# WarpDrive_201903.net
KiCad netlist of a schematic drawn in EAGLE
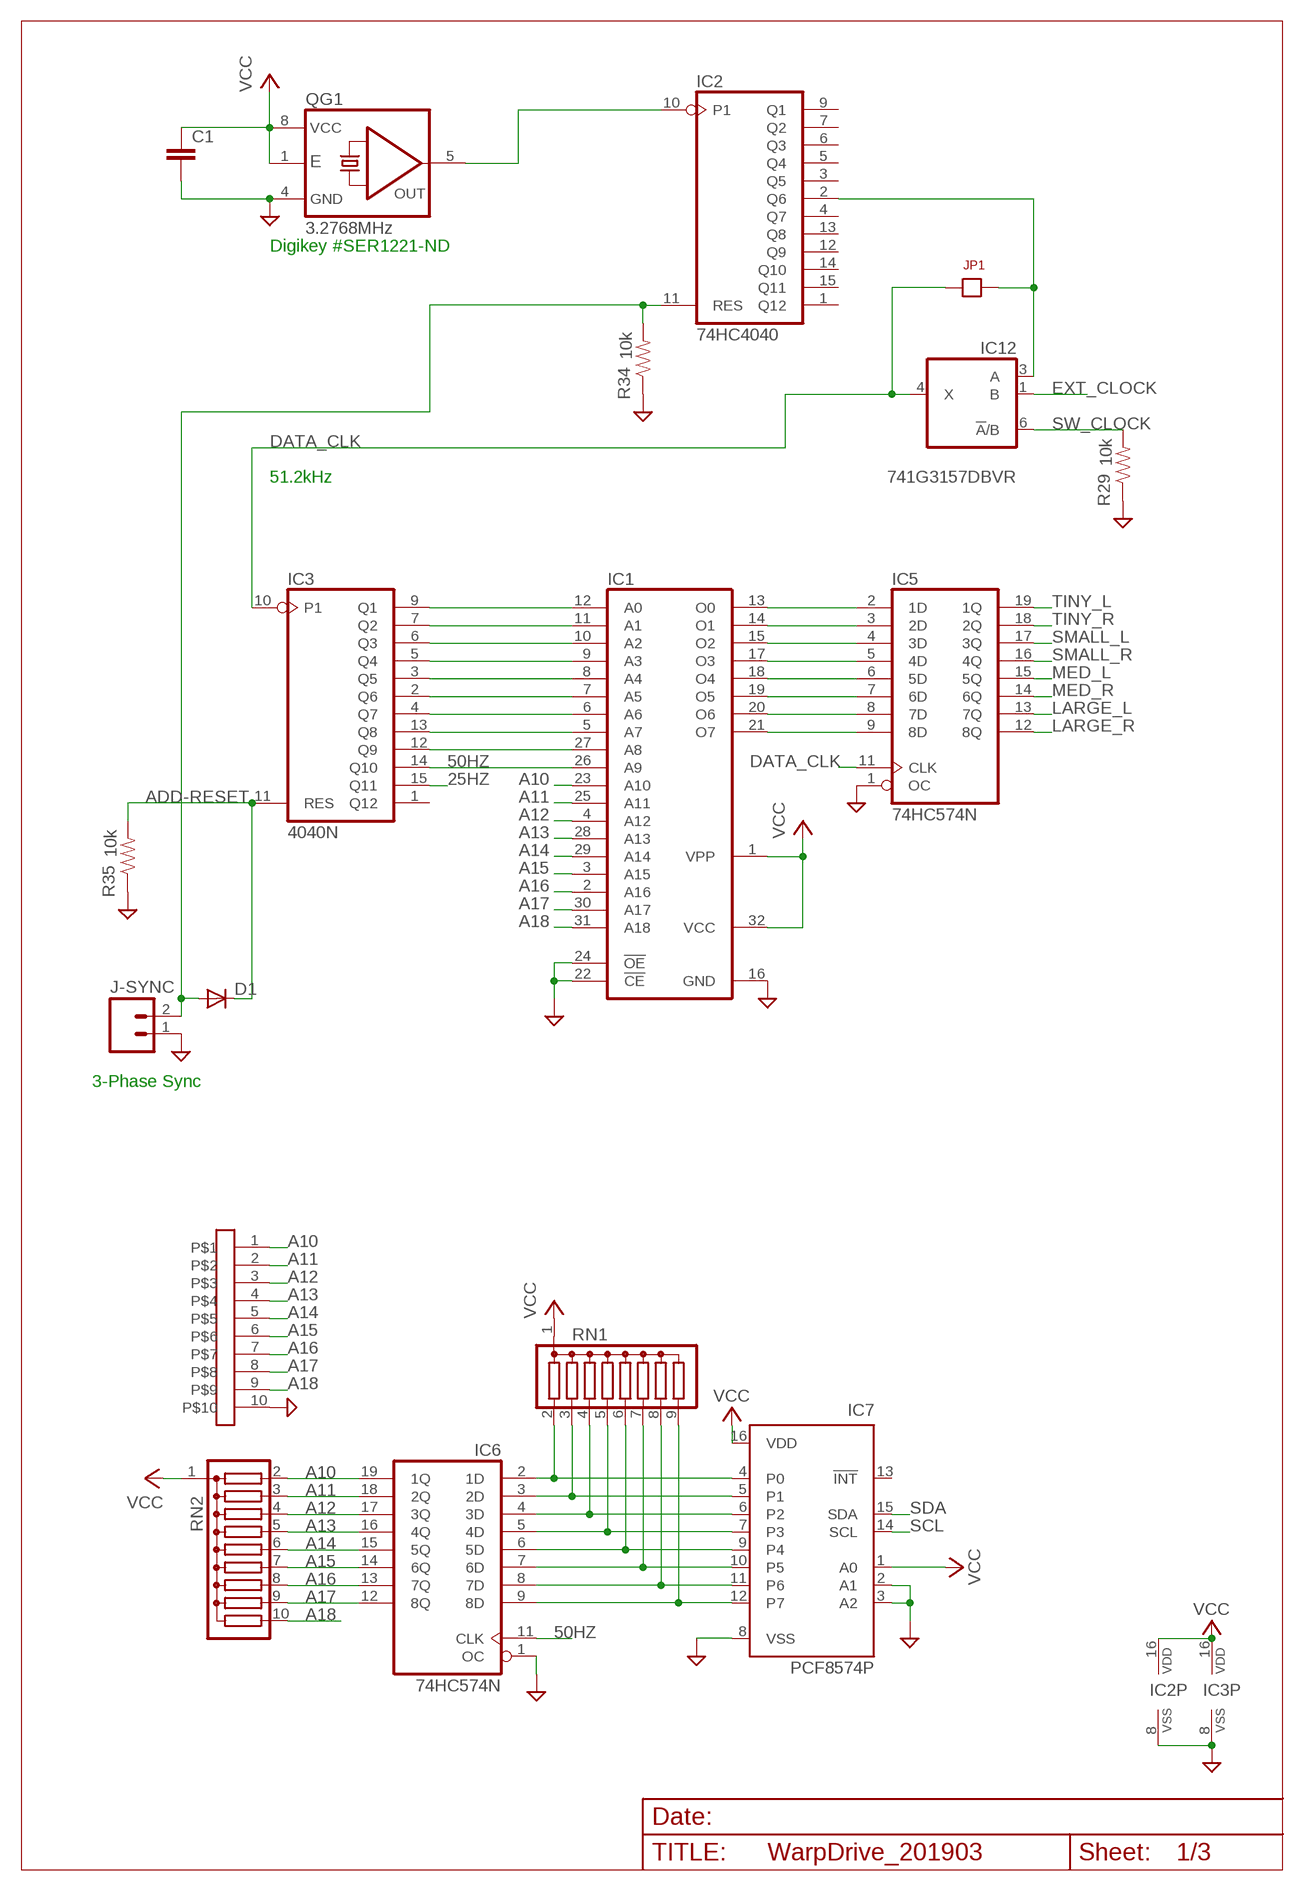
[diagram p0: schematic, sheet 1]
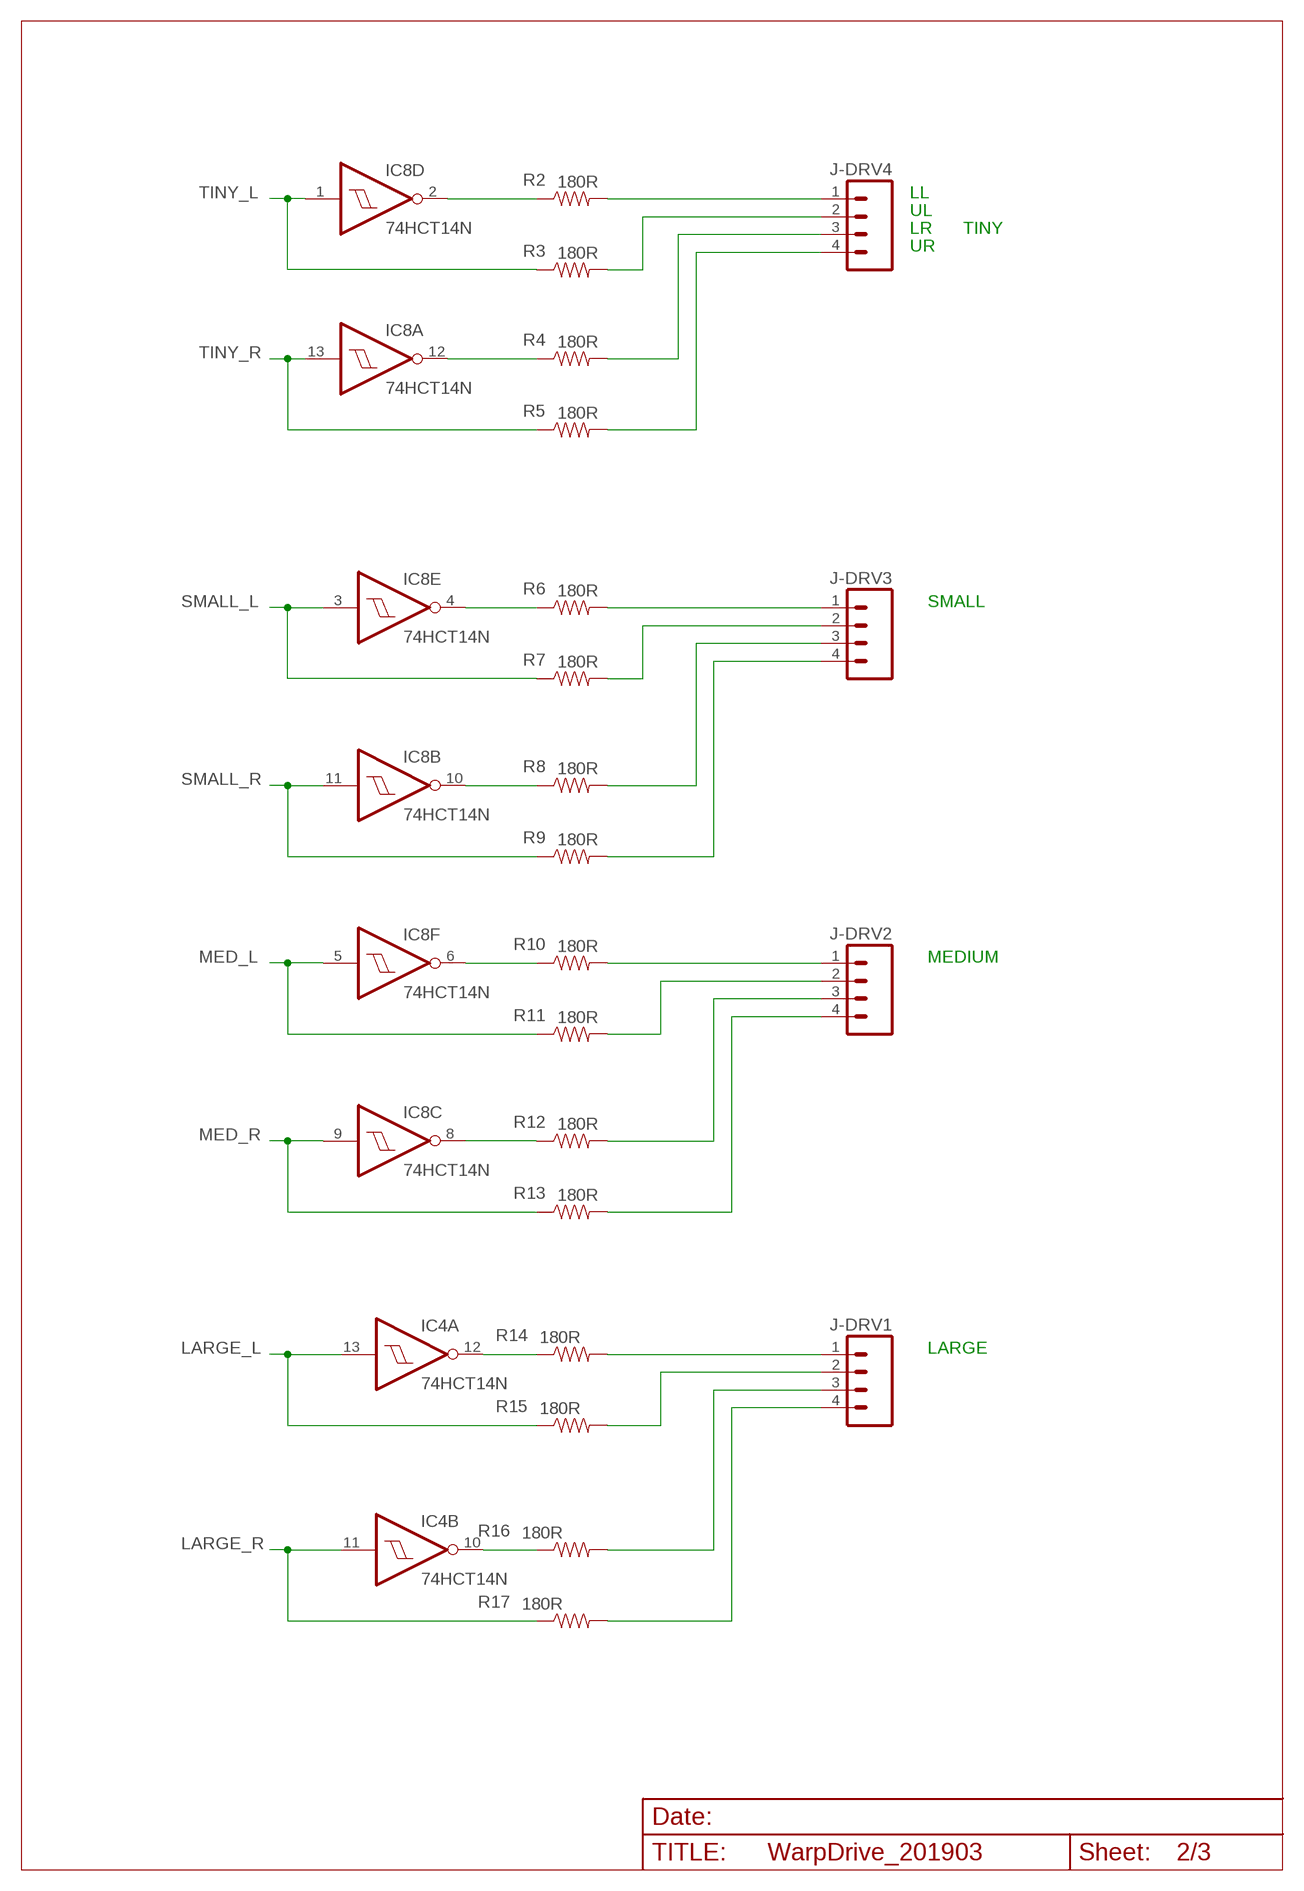
[diagram p1: schematic, sheet 2]
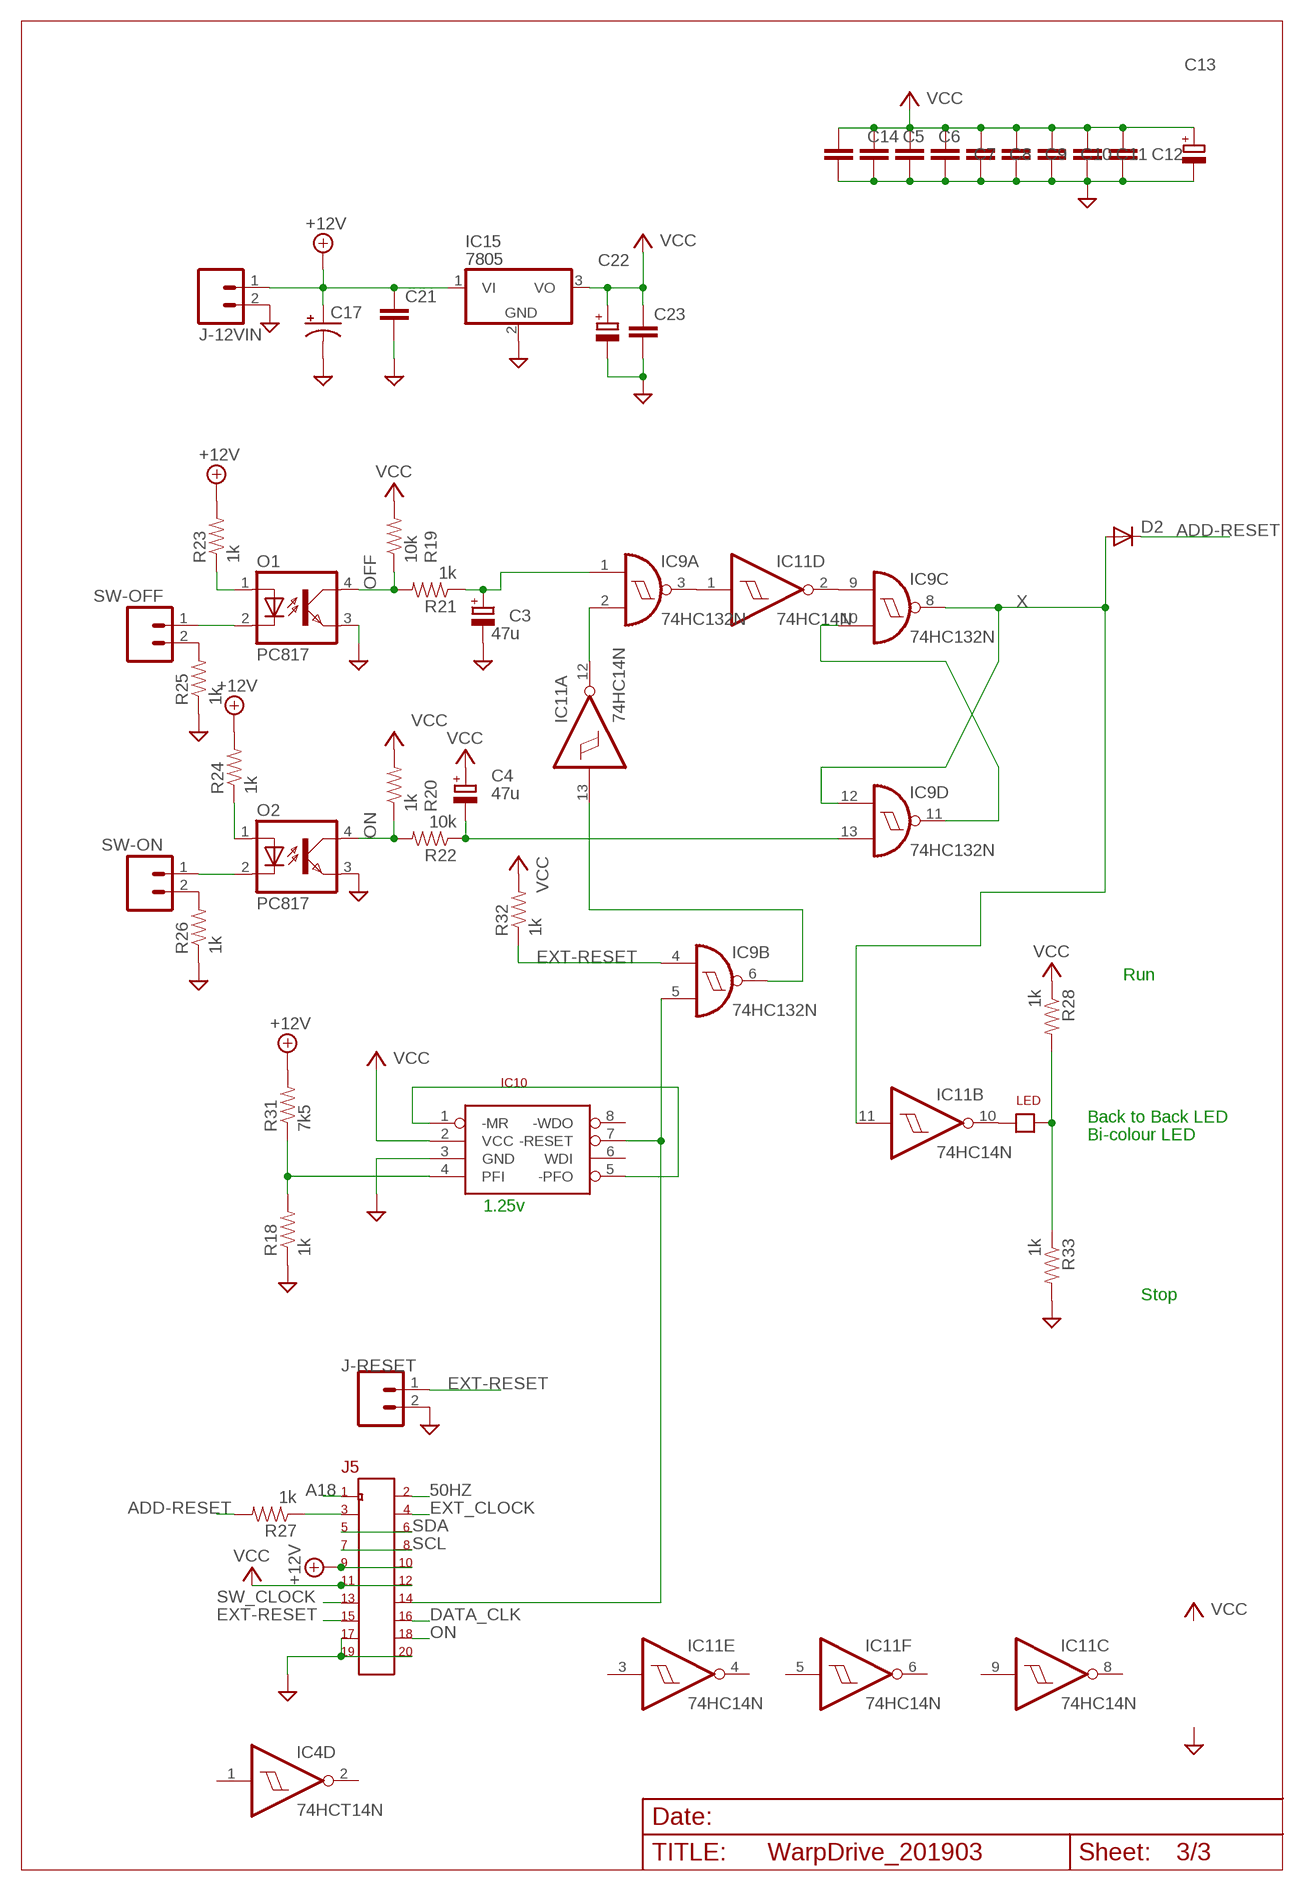
[diagram p2: schematic, sheet 3]

(export (version "E")
  (design (tool "Eeschema 10.0.6"))
  (components
    (comp (ref "IC4")
      (value "74HCT14N")
      (footprint "eagle-import:DIL14")
      (libsource (lib "eagle-import") (part "7414NHCT"))
    )
    (comp (ref "IC8")
      (value "74HCT14N")
      (footprint "eagle-import:DIL14")
      (libsource (lib "eagle-import") (part "7414NHCT"))
    )
    (comp (ref "J-DRV1")
      (value "MO4POL")
      (footprint "eagle-import:MOLEX-4")
      (libsource (lib "eagle-import") (part "MO4POL"))
    )
    (comp (ref "J-DRV2")
      (value "MO4POL")
      (footprint "eagle-import:MOLEX-4")
      (libsource (lib "eagle-import") (part "MO4POL"))
    )
    (comp (ref "J-DRV3")
      (value "MO4POL")
      (footprint "eagle-import:MOLEX-4")
      (libsource (lib "eagle-import") (part "MO4POL"))
    )
    (comp (ref "J-DRV4")
      (value "MO4POL")
      (footprint "eagle-import:MOLEX-4")
      (libsource (lib "eagle-import") (part "MO4POL"))
    )
    (comp (ref "R2")
      (value "180R")
      (footprint "eagle-import:AXIAL-0.4")
      (libsource (lib "eagle-import") (part "R4"))
    )
    (comp (ref "R3")
      (value "180R")
      (footprint "eagle-import:AXIAL-0.4")
      (libsource (lib "eagle-import") (part "R4"))
    )
    (comp (ref "R4")
      (value "180R")
      (footprint "eagle-import:AXIAL-0.4")
      (libsource (lib "eagle-import") (part "R4"))
    )
    (comp (ref "R5")
      (value "180R")
      (footprint "eagle-import:AXIAL-0.4")
      (libsource (lib "eagle-import") (part "R4"))
    )
    (comp (ref "R6")
      (value "180R")
      (footprint "eagle-import:AXIAL-0.4")
      (libsource (lib "eagle-import") (part "R4"))
    )
    (comp (ref "R7")
      (value "180R")
      (footprint "eagle-import:AXIAL-0.4")
      (libsource (lib "eagle-import") (part "R4"))
    )
    (comp (ref "R8")
      (value "180R")
      (footprint "eagle-import:AXIAL-0.4")
      (libsource (lib "eagle-import") (part "R4"))
    )
    (comp (ref "R9")
      (value "180R")
      (footprint "eagle-import:AXIAL-0.4")
      (libsource (lib "eagle-import") (part "R4"))
    )
    (comp (ref "R10")
      (value "180R")
      (footprint "eagle-import:AXIAL-0.4")
      (libsource (lib "eagle-import") (part "R4"))
    )
    (comp (ref "R11")
      (value "180R")
      (footprint "eagle-import:AXIAL-0.4")
      (libsource (lib "eagle-import") (part "R4"))
    )
    (comp (ref "R12")
      (value "180R")
      (footprint "eagle-import:AXIAL-0.4")
      (libsource (lib "eagle-import") (part "R4"))
    )
    (comp (ref "R13")
      (value "180R")
      (footprint "eagle-import:AXIAL-0.4")
      (libsource (lib "eagle-import") (part "R4"))
    )
    (comp (ref "R14")
      (value "180R")
      (footprint "eagle-import:AXIAL-0.4")
      (libsource (lib "eagle-import") (part "R4"))
    )
    (comp (ref "R15")
      (value "180R")
      (footprint "eagle-import:AXIAL-0.4")
      (libsource (lib "eagle-import") (part "R4"))
    )
    (comp (ref "R16")
      (value "180R")
      (footprint "eagle-import:AXIAL-0.4")
      (libsource (lib "eagle-import") (part "R4"))
    )
    (comp (ref "R17")
      (value "180R")
      (footprint "eagle-import:AXIAL-0.4")
      (libsource (lib "eagle-import") (part "R4"))
    )
    (comp (ref "C3")
      (value "47u")
      (footprint "eagle-import:CPOL-RADIAL-10UF-25V")
      (libsource (lib "eagle-import") (part "C-RB200100"))
    )
    (comp (ref "C4")
      (value "47u")
      (footprint "eagle-import:CPOL-RADIAL-10UF-25V")
      (libsource (lib "eagle-import") (part "C-RB200100"))
    )
    (comp (ref "C5")
      (value "BCAP")
      (footprint "eagle-import:BCAP")
      (libsource (lib "eagle-import") (part "BCAP"))
    )
    (comp (ref "C6")
      (value "BCAP")
      (footprint "eagle-import:BCAP")
      (libsource (lib "eagle-import") (part "BCAP"))
    )
    (comp (ref "C7")
      (value "BCAP")
      (footprint "eagle-import:BCAP")
      (libsource (lib "eagle-import") (part "BCAP"))
    )
    (comp (ref "C8")
      (value "BCAP")
      (footprint "eagle-import:BCAP")
      (libsource (lib "eagle-import") (part "BCAP"))
    )
    (comp (ref "C9")
      (value "BCAP")
      (footprint "eagle-import:BCAP")
      (libsource (lib "eagle-import") (part "BCAP"))
    )
    (comp (ref "C10")
      (value "BCAP")
      (footprint "eagle-import:BCAP")
      (libsource (lib "eagle-import") (part "BCAP"))
    )
    (comp (ref "C11")
      (value "BCAP")
      (footprint "eagle-import:BCAP")
      (libsource (lib "eagle-import") (part "BCAP"))
    )
    (comp (ref "C12")
      (value "BCAP")
      (footprint "eagle-import:BCAP")
      (libsource (lib "eagle-import") (part "BCAP"))
    )
    (comp (ref "C13")
      (value "C-RB200100")
      (footprint "eagle-import:CPOL-RADIAL-10UF-25V")
      (libsource (lib "eagle-import") (part "C-RB200100"))
    )
    (comp (ref "C14")
      (value "BCAP")
      (footprint "eagle-import:BCAP")
      (libsource (lib "eagle-import") (part "BCAP"))
    )
    (comp (ref "C17")
      (value "CAP_POLPTH1")
      (footprint "eagle-import:CPOL-RADIAL-100UF-25V")
      (libsource (lib "eagle-import") (part "CAP_POLPTH1"))
    )
    (comp (ref "C21")
      (value "BCAP")
      (footprint "eagle-import:BCAP")
      (libsource (lib "eagle-import") (part "BCAP"))
    )
    (comp (ref "C22")
      (value "C-RB200100")
      (footprint "eagle-import:CPOL-RADIAL-10UF-25V")
      (libsource (lib "eagle-import") (part "C-RB200100"))
    )
    (comp (ref "C23")
      (value "BCAP")
      (footprint "eagle-import:BCAP")
      (libsource (lib "eagle-import") (part "BCAP"))
    )
    (comp (ref "D2")
      (value "1N4148DO35-7")
      (footprint "eagle-import:D3")
      (libsource (lib "eagle-import") (part "1N4148DO35-7"))
    )
    (comp (ref "IC9")
      (value "74HC132N")
      (footprint "eagle-import:DIL14")
      (libsource (lib "eagle-import") (part "74132NHC"))
    )
    (comp (ref "IC10")
      (value "ADM705")
      (footprint "eagle-import:DIL08")
      (libsource (lib "eagle-import") (part "ADM705"))
    )
    (comp (ref "IC11")
      (value "74HC14N")
      (footprint "eagle-import:DIL14")
      (libsource (lib "eagle-import") (part "7414NHC"))
    )
    (comp (ref "IC15")
      (value "7805")
      (footprint "eagle-import:TO220V")
      (libsource (lib "eagle-import") (part "78TV05"))
    )
    (comp (ref "J-12VIN")
      (value "MO2POL")
      (footprint "eagle-import:MOLEX-1X2")
      (libsource (lib "eagle-import") (part "MO2POL"))
    )
    (comp (ref "J-RESET")
      (value "MO2POL")
      (footprint "eagle-import:MOLEX-1X2")
      (libsource (lib "eagle-import") (part "MO2POL"))
    )
    (comp (ref "J5")
      (value "IDC20IDC20-SMALL")
      (footprint "eagle-import:IDC20-SMALL")
      (libsource (lib "eagle-import") (part "IDC20IDC20-SMALL"))
    )
    (comp (ref "LED")
      (value "JP1")
      (footprint "eagle-import:JP1")
      (libsource (lib "eagle-import") (part "JP1"))
    )
    (comp (ref "O1")
      (value "PC817")
      (footprint "eagle-import:DIL04")
      (fields (field (name "MPN") "PC817X4J000F"))
      (libsource (lib "eagle-import") (part "PC817"))
    )
    (comp (ref "O2")
      (value "PC817")
      (footprint "eagle-import:DIL04")
      (fields (field (name "MPN") "PC817X4J000F"))
      (libsource (lib "eagle-import") (part "PC817"))
    )
    (comp (ref "R18")
      (value "1k")
      (footprint "eagle-import:AXIAL-0.4")
      (libsource (lib "eagle-import") (part "R4"))
    )
    (comp (ref "R19")
      (value "10k")
      (footprint "eagle-import:AXIAL-0.4")
      (libsource (lib "eagle-import") (part "R4"))
    )
    (comp (ref "R20")
      (value "1k")
      (footprint "eagle-import:AXIAL-0.4")
      (libsource (lib "eagle-import") (part "R4"))
    )
    (comp (ref "R21")
      (value "1k")
      (footprint "eagle-import:AXIAL-0.4")
      (libsource (lib "eagle-import") (part "R4"))
    )
    (comp (ref "R22")
      (value "10k")
      (footprint "eagle-import:AXIAL-0.4")
      (libsource (lib "eagle-import") (part "R4"))
    )
    (comp (ref "R23")
      (value "1k")
      (footprint "eagle-import:AXIAL-0.4")
      (libsource (lib "eagle-import") (part "R4"))
    )
    (comp (ref "R24")
      (value "1k")
      (footprint "eagle-import:AXIAL-0.4")
      (libsource (lib "eagle-import") (part "R4"))
    )
    (comp (ref "R25")
      (value "1k")
      (footprint "eagle-import:AXIAL-0.4")
      (libsource (lib "eagle-import") (part "R4"))
    )
    (comp (ref "R26")
      (value "1k")
      (footprint "eagle-import:AXIAL-0.4")
      (libsource (lib "eagle-import") (part "R4"))
    )
    (comp (ref "R27")
      (value "1k")
      (footprint "eagle-import:AXIAL-0.4")
      (libsource (lib "eagle-import") (part "R4"))
    )
    (comp (ref "R28")
      (value "1k")
      (footprint "eagle-import:AXIAL-0.4")
      (libsource (lib "eagle-import") (part "R4"))
    )
    (comp (ref "R31")
      (value "7k5")
      (footprint "eagle-import:AXIAL-0.4")
      (libsource (lib "eagle-import") (part "R4"))
    )
    (comp (ref "R32")
      (value "1k")
      (footprint "eagle-import:AXIAL-0.4")
      (libsource (lib "eagle-import") (part "R4"))
    )
    (comp (ref "R33")
      (value "1k")
      (footprint "eagle-import:AXIAL-0.4")
      (libsource (lib "eagle-import") (part "R4"))
    )
    (comp (ref "SW-OFF")
      (value "MO2POL")
      (footprint "eagle-import:MOLEX-1X2")
      (libsource (lib "eagle-import") (part "MO2POL"))
    )
    (comp (ref "SW-ON")
      (value "MO2POL")
      (footprint "eagle-import:MOLEX-1X2")
      (libsource (lib "eagle-import") (part "MO2POL"))
    )
    (comp (ref "C1")
      (value "BCAP")
      (footprint "eagle-import:BCAP")
      (libsource (lib "eagle-import") (part "BCAP"))
    )
    (comp (ref "D1")
      (value "1N4148DO35-7")
      (footprint "eagle-import:D3")
      (libsource (lib "eagle-import") (part "1N4148DO35-7"))
    )
    (comp (ref "IC1")
      (value "27C4001D")
      (footprint "eagle-import:DIL32")
      (fields (field (name "MPN") "M27C4001-12B1"))
      (libsource (lib "eagle-import") (part "27C4001D"))
    )
    (comp (ref "IC2")
      (value "74HC4040")
      (footprint "eagle-import:DIL16")
      (libsource (lib "eagle-import") (part "4040N"))
    )
    (comp (ref "IC3")
      (value "4040N")
      (footprint "eagle-import:DIL16")
      (libsource (lib "eagle-import") (part "4040N"))
    )
    (comp (ref "IC5")
      (value "74HC574N")
      (footprint "eagle-import:DIL20")
      (libsource (lib "eagle-import") (part "74574NHC"))
    )
    (comp (ref "IC6")
      (value "74HC574N")
      (footprint "eagle-import:DIL20")
      (libsource (lib "eagle-import") (part "74574NHC"))
    )
    (comp (ref "IC7")
      (value "PCF8574P")
      (footprint "eagle-import:DIL16")
      (fields (field (name "MPN") "PCF8574PN"))
      (libsource (lib "eagle-import") (part "PCF8574P"))
    )
    (comp (ref "IC12")
      (value "741G3157DBVR")
      (footprint "eagle-import:DBV_R-PDSO-G6")
      (libsource (lib "eagle-import") (part "741G3157DBVR"))
    )
    (comp (ref "J-SYNC")
      (value "MO2POL")
      (footprint "eagle-import:MOLEX-1X2")
      (libsource (lib "eagle-import") (part "Andrew_Connectors_MO2POL"))
    )
    (comp (ref "J1")
      (value "SIL-STACK-10")
      (footprint "eagle-import:SIL-STACK-10")
      (libsource (lib "eagle-import") (part "SIL-STACK-10"))
    )
    (comp (ref "JP1")
      (value "JP1")
      (footprint "eagle-import:JP1")
      (libsource (lib "eagle-import") (part "JP1"))
    )
    (comp (ref "QG1")
      (value "3.2768MHz")
      (footprint "eagle-import:DIL08-4")
      (fields (field (name "MPN") "SG531P16MHZ"))
      (libsource (lib "eagle-import") (part "SG531"))
    )
    (comp (ref "R29")
      (value "10k")
      (footprint "eagle-import:AXIAL-0.4")
      (libsource (lib "eagle-import") (part "R4"))
    )
    (comp (ref "R34")
      (value "10k")
      (footprint "eagle-import:AXIAL-0.4")
      (libsource (lib "eagle-import") (part "R4"))
    )
    (comp (ref "R35")
      (value "10k")
      (footprint "eagle-import:AXIAL-0.4")
      (libsource (lib "eagle-import") (part "R4"))
    )
    (comp (ref "RN1")
      (value "G08R")
      (footprint "eagle-import:SIL9")
      (libsource (lib "eagle-import") (part "G08R"))
    )
    (comp (ref "RN2")
      (value "G09R")
      (footprint "eagle-import:SIL10")
      (libsource (lib "eagle-import") (part "G09R"))
    )
  )
  (nets
    (net (code "1") (name "+12V") (class "Default")
      (node (ref "C17") (pin "1") (pinfunction "+_1") (pintype "passive"))
      (node (ref "C21") (pin "1") (pinfunction "1_1") (pintype "passive"))
      (node (ref "IC15") (pin "1") (pinfunction "VI_1") (pintype "input"))
      (node (ref "J-12VIN") (pin "1") (pinfunction "1_1") (pintype "passive"))
      (node (ref "J5") (pin "10") (pinfunction "10_10") (pintype "bidirectional"))
      (node (ref "J5") (pin "9") (pinfunction "9_9") (pintype "bidirectional"))
      (node (ref "R23") (pin "P$2") (pinfunction "2_P$2") (pintype "passive"))
      (node (ref "R24") (pin "P$2") (pinfunction "2_P$2") (pintype "passive"))
      (node (ref "R31") (pin "P$2") (pinfunction "2_P$2") (pintype "passive"))
    )
    (net (code "2") (name "25HZ") (class "Default")
      (node (ref "IC3") (pin "15") (pinfunction "Q11_15") (pintype "output"))
    )
    (net (code "3") (name "50HZ") (class "Default")
      (node (ref "IC1") (pin "26") (pinfunction "A9_26") (pintype "input"))
      (node (ref "IC3") (pin "14") (pinfunction "Q10_14") (pintype "output"))
      (node (ref "IC6") (pin "11") (pinfunction "CLK_11") (pintype "input"))
      (node (ref "J5") (pin "2") (pinfunction "2_2") (pintype "bidirectional"))
    )
    (net (code "4") (name "A10") (class "Default")
      (node (ref "IC1") (pin "23") (pinfunction "A10_23") (pintype "input"))
      (node (ref "IC6") (pin "19") (pinfunction "1Q_19") (pintype "tri_state"))
      (node (ref "J1") (pin "1") (pinfunction "P$1_1") (pintype "bidirectional"))
      (node (ref "RN2") (pin "2") (pinfunction "2_2") (pintype "passive"))
    )
    (net (code "5") (name "A11") (class "Default")
      (node (ref "IC1") (pin "25") (pinfunction "A11_25") (pintype "input"))
      (node (ref "IC6") (pin "18") (pinfunction "2Q_18") (pintype "tri_state"))
      (node (ref "J1") (pin "2") (pinfunction "P$2_2") (pintype "bidirectional"))
      (node (ref "RN2") (pin "3") (pinfunction "3_3") (pintype "passive"))
    )
    (net (code "6") (name "A12") (class "Default")
      (node (ref "IC1") (pin "4") (pinfunction "A12_4") (pintype "input"))
      (node (ref "IC6") (pin "17") (pinfunction "3Q_17") (pintype "tri_state"))
      (node (ref "J1") (pin "3") (pinfunction "P$3_3") (pintype "bidirectional"))
      (node (ref "RN2") (pin "4") (pinfunction "4_4") (pintype "passive"))
    )
    (net (code "7") (name "A13") (class "Default")
      (node (ref "IC1") (pin "28") (pinfunction "A13_28") (pintype "input"))
      (node (ref "IC6") (pin "16") (pinfunction "4Q_16") (pintype "tri_state"))
      (node (ref "J1") (pin "4") (pinfunction "P$4_4") (pintype "bidirectional"))
      (node (ref "RN2") (pin "5") (pinfunction "5_5") (pintype "passive"))
    )
    (net (code "8") (name "A14") (class "Default")
      (node (ref "IC1") (pin "29") (pinfunction "A14_29") (pintype "input"))
      (node (ref "IC6") (pin "15") (pinfunction "5Q_15") (pintype "tri_state"))
      (node (ref "J1") (pin "5") (pinfunction "P$5_5") (pintype "bidirectional"))
      (node (ref "RN2") (pin "6") (pinfunction "6_6") (pintype "passive"))
    )
    (net (code "9") (name "A15") (class "Default")
      (node (ref "IC1") (pin "3") (pinfunction "A15_3") (pintype "input"))
      (node (ref "IC6") (pin "14") (pinfunction "6Q_14") (pintype "tri_state"))
      (node (ref "J1") (pin "6") (pinfunction "P$6_6") (pintype "bidirectional"))
      (node (ref "RN2") (pin "7") (pinfunction "7_7") (pintype "passive"))
    )
    (net (code "10") (name "A16") (class "Default")
      (node (ref "IC1") (pin "2") (pinfunction "A16_2") (pintype "input"))
      (node (ref "IC6") (pin "13") (pinfunction "7Q_13") (pintype "tri_state"))
      (node (ref "J1") (pin "7") (pinfunction "P$7_7") (pintype "bidirectional"))
      (node (ref "RN2") (pin "8") (pinfunction "8_8") (pintype "passive"))
    )
    (net (code "11") (name "A17") (class "Default")
      (node (ref "IC1") (pin "30") (pinfunction "A17_30") (pintype "input"))
      (node (ref "IC6") (pin "12") (pinfunction "8Q_12") (pintype "tri_state"))
      (node (ref "J1") (pin "8") (pinfunction "P$8_8") (pintype "bidirectional"))
      (node (ref "RN2") (pin "9") (pinfunction "9_9") (pintype "passive"))
    )
    (net (code "12") (name "A18") (class "Default")
      (node (ref "IC1") (pin "31") (pinfunction "A18_31") (pintype "input"))
      (node (ref "J1") (pin "9") (pinfunction "P$9_9") (pintype "bidirectional"))
      (node (ref "J5") (pin "1") (pinfunction "1_1") (pintype "bidirectional"))
      (node (ref "RN2") (pin "10") (pinfunction "10_10") (pintype "passive"))
    )
    (net (code "13") (name "ADD-RESET") (class "Default")
      (node (ref "D1") (pin "C") (pinfunction "C_C") (pintype "passive"))
      (node (ref "D2") (pin "C") (pinfunction "C_C") (pintype "passive"))
      (node (ref "IC3") (pin "11") (pinfunction "RES_11") (pintype "input"))
      (node (ref "R27") (pin "P$2") (pinfunction "2_P$2") (pintype "passive"))
      (node (ref "R35") (pin "P$2") (pinfunction "2_P$2") (pintype "passive"))
    )
    (net (code "14") (name "DATA_CLK") (class "Default")
      (node (ref "IC12") (pin "4") (pinfunction "X_4") (pintype "bidirectional"))
      (node (ref "IC3") (pin "10") (pinfunction "P1_10") (pintype "input"))
      (node (ref "IC5") (pin "11") (pinfunction "CLK_11") (pintype "input"))
      (node (ref "J5") (pin "16") (pinfunction "16_16") (pintype "bidirectional"))
      (node (ref "JP1") (pin "1") (pinfunction "1_1") (pintype "bidirectional"))
    )
    (net (code "15") (name "EXT-RESET") (class "Default")
      (node (ref "IC9") (pin "4") (pinfunction "I0_4") (pintype "input"))
      (node (ref "J-RESET") (pin "1") (pinfunction "1_1") (pintype "passive"))
      (node (ref "J5") (pin "15") (pinfunction "15_15") (pintype "bidirectional"))
      (node (ref "R32") (pin "P$1") (pinfunction "1_P$1") (pintype "passive"))
    )
    (net (code "16") (name "EXT_CLOCK") (class "Default")
      (node (ref "IC12") (pin "1") (pinfunction "B_1") (pintype "bidirectional"))
      (node (ref "J5") (pin "4") (pinfunction "4_4") (pintype "bidirectional"))
    )
    (net (code "17") (name "GND") (class "Default")
      (node (ref "C1") (pin "2") (pinfunction "2_2") (pintype "passive"))
      (node (ref "C10") (pin "2") (pinfunction "2_2") (pintype "passive"))
      (node (ref "C11") (pin "2") (pinfunction "2_2") (pintype "passive"))
      (node (ref "C12") (pin "2") (pinfunction "2_2") (pintype "passive"))
      (node (ref "C13") (pin "2") (pinfunction "-_2") (pintype "passive"))
      (node (ref "C14") (pin "2") (pinfunction "2_2") (pintype "passive"))
      (node (ref "C17") (pin "2") (pinfunction "-_2") (pintype "passive"))
      (node (ref "C21") (pin "2") (pinfunction "2_2") (pintype "passive"))
      (node (ref "C22") (pin "2") (pinfunction "-_2") (pintype "passive"))
      (node (ref "C23") (pin "2") (pinfunction "2_2") (pintype "passive"))
      (node (ref "C3") (pin "2") (pinfunction "-_2") (pintype "passive"))
      (node (ref "C5") (pin "2") (pinfunction "2_2") (pintype "passive"))
      (node (ref "C6") (pin "2") (pinfunction "2_2") (pintype "passive"))
      (node (ref "C7") (pin "2") (pinfunction "2_2") (pintype "passive"))
      (node (ref "C8") (pin "2") (pinfunction "2_2") (pintype "passive"))
      (node (ref "C9") (pin "2") (pinfunction "2_2") (pintype "passive"))
      (node (ref "IC1") (pin "16") (pinfunction "GND_16") (pintype "power_in"))
      (node (ref "IC1") (pin "22") (pinfunction "~{CE}_22") (pintype "input"))
      (node (ref "IC1") (pin "24") (pinfunction "~{OE}_24") (pintype "input"))
      (node (ref "IC10") (pin "3") (pinfunction "GND_3") (pintype "bidirectional"))
      (node (ref "IC15") (pin "2") (pinfunction "GND_2") (pintype "passive"))
      (node (ref "IC2") (pin "8") (pinfunction "VSS_8") (pintype "power_in"))
      (node (ref "IC3") (pin "8") (pinfunction "VSS_8") (pintype "power_in"))
      (node (ref "IC5") (pin "1") (pinfunction "OC_1") (pintype "input"))
      (node (ref "IC6") (pin "1") (pinfunction "OC_1") (pintype "input"))
      (node (ref "IC7") (pin "2") (pinfunction "A1_2") (pintype "input"))
      (node (ref "IC7") (pin "3") (pinfunction "A2_3") (pintype "input"))
      (node (ref "IC7") (pin "8") (pinfunction "VSS_8") (pintype "power_in"))
      (node (ref "J-12VIN") (pin "2") (pinfunction "2_2") (pintype "passive"))
      (node (ref "J-RESET") (pin "2") (pinfunction "2_2") (pintype "passive"))
      (node (ref "J-SYNC") (pin "1") (pinfunction "1_1") (pintype "passive"))
      (node (ref "J1") (pin "10") (pinfunction "P$10_10") (pintype "bidirectional"))
      (node (ref "J5") (pin "17") (pinfunction "17_17") (pintype "bidirectional"))
      (node (ref "J5") (pin "19") (pinfunction "19_19") (pintype "bidirectional"))
      (node (ref "J5") (pin "20") (pinfunction "20_20") (pintype "bidirectional"))
      (node (ref "O1") (pin "3") (pinfunction "EMIT_3") (pintype "passive"))
      (node (ref "O2") (pin "3") (pinfunction "EMIT_3") (pintype "passive"))
      (node (ref "QG1") (pin "4") (pinfunction "GND_4") (pintype "power_in"))
      (node (ref "R18") (pin "P$1") (pinfunction "1_P$1") (pintype "passive"))
      (node (ref "R25") (pin "P$1") (pinfunction "1_P$1") (pintype "passive"))
      (node (ref "R26") (pin "P$1") (pinfunction "1_P$1") (pintype "passive"))
      (node (ref "R29") (pin "P$1") (pinfunction "1_P$1") (pintype "passive"))
      (node (ref "R33") (pin "P$2") (pinfunction "2_P$2") (pintype "passive"))
      (node (ref "R34") (pin "P$1") (pinfunction "1_P$1") (pintype "passive"))
      (node (ref "R35") (pin "P$1") (pinfunction "1_P$1") (pintype "passive"))
    )
    (net (code "18") (name "LARGE_L") (class "Default")
      (node (ref "IC4") (pin "13") (pinfunction "I_13") (pintype "input"))
      (node (ref "IC5") (pin "13") (pinfunction "7Q_13") (pintype "tri_state"))
      (node (ref "R15") (pin "P$1") (pinfunction "1_P$1") (pintype "passive"))
    )
    (net (code "19") (name "LARGE_R") (class "Default")
      (node (ref "IC4") (pin "11") (pinfunction "I_11") (pintype "input"))
      (node (ref "IC5") (pin "12") (pinfunction "8Q_12") (pintype "tri_state"))
      (node (ref "R17") (pin "P$1") (pinfunction "1_P$1") (pintype "passive"))
    )
    (net (code "20") (name "MED_L") (class "Default")
      (node (ref "IC5") (pin "15") (pinfunction "5Q_15") (pintype "tri_state"))
      (node (ref "IC8") (pin "5") (pinfunction "I_5") (pintype "input"))
      (node (ref "R11") (pin "P$1") (pinfunction "1_P$1") (pintype "passive"))
    )
    (net (code "21") (name "MED_R") (class "Default")
      (node (ref "IC5") (pin "14") (pinfunction "6Q_14") (pintype "tri_state"))
      (node (ref "IC8") (pin "9") (pinfunction "I_9") (pintype "input"))
      (node (ref "R13") (pin "P$1") (pinfunction "1_P$1") (pintype "passive"))
    )
    (net (code "22") (name "Net-(C3-+)") (class "Default")
      (node (ref "C3") (pin "1") (pinfunction "+_1") (pintype "passive"))
      (node (ref "IC9") (pin "1") (pinfunction "I0_1") (pintype "input"))
      (node (ref "R21") (pin "P$1") (pinfunction "1_P$1") (pintype "passive"))
    )
    (net (code "23") (name "Net-(C4--)") (class "Default")
      (node (ref "C4") (pin "2") (pinfunction "-_2") (pintype "passive"))
      (node (ref "IC9") (pin "13") (pinfunction "I1_13") (pintype "input"))
      (node (ref "R22") (pin "P$1") (pinfunction "1_P$1") (pintype "passive"))
    )
    (net (code "24") (name "Net-(IC1-A0)") (class "Default")
      (node (ref "IC1") (pin "12") (pinfunction "A0_12") (pintype "input"))
      (node (ref "IC3") (pin "9") (pinfunction "Q1_9") (pintype "output"))
    )
    (net (code "25") (name "Net-(IC1-A1)") (class "Default")
      (node (ref "IC1") (pin "11") (pinfunction "A1_11") (pintype "input"))
      (node (ref "IC3") (pin "7") (pinfunction "Q2_7") (pintype "output"))
    )
    (net (code "26") (name "Net-(IC1-A2)") (class "Default")
      (node (ref "IC1") (pin "10") (pinfunction "A2_10") (pintype "input"))
      (node (ref "IC3") (pin "6") (pinfunction "Q3_6") (pintype "output"))
    )
    (net (code "27") (name "Net-(IC1-A3)") (class "Default")
      (node (ref "IC1") (pin "9") (pinfunction "A3_9") (pintype "input"))
      (node (ref "IC3") (pin "5") (pinfunction "Q4_5") (pintype "output"))
    )
    (net (code "28") (name "Net-(IC1-A4)") (class "Default")
      (node (ref "IC1") (pin "8") (pinfunction "A4_8") (pintype "input"))
      (node (ref "IC3") (pin "3") (pinfunction "Q5_3") (pintype "output"))
    )
    (net (code "29") (name "Net-(IC1-A5)") (class "Default")
      (node (ref "IC1") (pin "7") (pinfunction "A5_7") (pintype "input"))
      (node (ref "IC3") (pin "2") (pinfunction "Q6_2") (pintype "output"))
    )
    (net (code "30") (name "Net-(IC1-A6)") (class "Default")
      (node (ref "IC1") (pin "6") (pinfunction "A6_6") (pintype "input"))
      (node (ref "IC3") (pin "4") (pinfunction "Q7_4") (pintype "output"))
    )
    (net (code "31") (name "Net-(IC1-A7)") (class "Default")
      (node (ref "IC1") (pin "5") (pinfunction "A7_5") (pintype "input"))
      (node (ref "IC3") (pin "13") (pinfunction "Q8_13") (pintype "output"))
    )
    (net (code "32") (name "Net-(IC1-A8)") (class "Default")
      (node (ref "IC1") (pin "27") (pinfunction "A8_27") (pintype "input"))
      (node (ref "IC3") (pin "12") (pinfunction "Q9_12") (pintype "output"))
    )
    (net (code "33") (name "Net-(IC1-O0)") (class "Default")
      (node (ref "IC1") (pin "13") (pinfunction "O0_13") (pintype "tri_state"))
      (node (ref "IC5") (pin "2") (pinfunction "1D_2") (pintype "input"))
    )
    (net (code "34") (name "Net-(IC1-O1)") (class "Default")
      (node (ref "IC1") (pin "14") (pinfunction "O1_14") (pintype "tri_state"))
      (node (ref "IC5") (pin "3") (pinfunction "2D_3") (pintype "input"))
    )
    (net (code "35") (name "Net-(IC1-O2)") (class "Default")
      (node (ref "IC1") (pin "15") (pinfunction "O2_15") (pintype "tri_state"))
      (node (ref "IC5") (pin "4") (pinfunction "3D_4") (pintype "input"))
    )
    (net (code "36") (name "Net-(IC1-O3)") (class "Default")
      (node (ref "IC1") (pin "17") (pinfunction "O3_17") (pintype "tri_state"))
      (node (ref "IC5") (pin "5") (pinfunction "4D_5") (pintype "input"))
    )
    (net (code "37") (name "Net-(IC1-O4)") (class "Default")
      (node (ref "IC1") (pin "18") (pinfunction "O4_18") (pintype "tri_state"))
      (node (ref "IC5") (pin "6") (pinfunction "5D_6") (pintype "input"))
    )
    (net (code "38") (name "Net-(IC1-O5)") (class "Default")
      (node (ref "IC1") (pin "19") (pinfunction "O5_19") (pintype "tri_state"))
      (node (ref "IC5") (pin "7") (pinfunction "6D_7") (pintype "input"))
    )
    (net (code "39") (name "Net-(IC1-O6)") (class "Default")
      (node (ref "IC1") (pin "20") (pinfunction "O6_20") (pintype "tri_state"))
      (node (ref "IC5") (pin "8") (pinfunction "7D_8") (pintype "input"))
    )
    (net (code "40") (name "Net-(IC1-O7)") (class "Default")
      (node (ref "IC1") (pin "21") (pinfunction "O7_21") (pintype "tri_state"))
      (node (ref "IC5") (pin "9") (pinfunction "8D_9") (pintype "input"))
    )
    (net (code "41") (name "Net-(IC2A-P1)") (class "Default")
      (node (ref "IC2") (pin "10") (pinfunction "P1_10") (pintype "input"))
      (node (ref "QG1") (pin "5") (pinfunction "OUT_5") (pintype "output"))
    )
    (net (code "42") (name "Net-(IC2A-RES)") (class "Default")
      (node (ref "D1") (pin "A") (pinfunction "A_A") (pintype "passive"))
      (node (ref "IC2") (pin "11") (pinfunction "RES_11") (pintype "input"))
      (node (ref "J-SYNC") (pin "2") (pinfunction "2_2") (pintype "passive"))
      (node (ref "R34") (pin "P$2") (pinfunction "2_P$2") (pintype "passive"))
    )
    (net (code "43") (name "Net-(IC4A-O)") (class "Default")
      (node (ref "IC4") (pin "12") (pinfunction "O_12") (pintype "output"))
      (node (ref "R14") (pin "P$1") (pinfunction "1_P$1") (pintype "passive"))
    )
    (net (code "44") (name "Net-(IC4B-O)") (class "Default")
      (node (ref "IC4") (pin "10") (pinfunction "O_10") (pintype "output"))
      (node (ref "R16") (pin "P$1") (pinfunction "1_P$1") (pintype "passive"))
    )
    (net (code "45") (name "Net-(IC6A-1D)") (class "Default")
      (node (ref "IC6") (pin "2") (pinfunction "1D_2") (pintype "input"))
      (node (ref "IC7") (pin "4") (pinfunction "P0_4") (pintype "bidirectional"))
      (node (ref "RN1") (pin "2") (pinfunction "2_2") (pintype "passive"))
    )
    (net (code "46") (name "Net-(IC6A-2D)") (class "Default")
      (node (ref "IC6") (pin "3") (pinfunction "2D_3") (pintype "input"))
      (node (ref "IC7") (pin "5") (pinfunction "P1_5") (pintype "bidirectional"))
      (node (ref "RN1") (pin "3") (pinfunction "3_3") (pintype "passive"))
    )
    (net (code "47") (name "Net-(IC6A-3D)") (class "Default")
      (node (ref "IC6") (pin "4") (pinfunction "3D_4") (pintype "input"))
      (node (ref "IC7") (pin "6") (pinfunction "P2_6") (pintype "bidirectional"))
      (node (ref "RN1") (pin "4") (pinfunction "4_4") (pintype "passive"))
    )
    (net (code "48") (name "Net-(IC6A-4D)") (class "Default")
      (node (ref "IC6") (pin "5") (pinfunction "4D_5") (pintype "input"))
      (node (ref "IC7") (pin "7") (pinfunction "P3_7") (pintype "bidirectional"))
      (node (ref "RN1") (pin "5") (pinfunction "5_5") (pintype "passive"))
    )
    (net (code "49") (name "Net-(IC6A-5D)") (class "Default")
      (node (ref "IC6") (pin "6") (pinfunction "5D_6") (pintype "input"))
      (node (ref "IC7") (pin "9") (pinfunction "P4_9") (pintype "bidirectional"))
      (node (ref "RN1") (pin "6") (pinfunction "6_6") (pintype "passive"))
    )
    (net (code "50") (name "Net-(IC6A-6D)") (class "Default")
      (node (ref "IC6") (pin "7") (pinfunction "6D_7") (pintype "input"))
      (node (ref "IC7") (pin "10") (pinfunction "P5_10") (pintype "bidirectional"))
      (node (ref "RN1") (pin "7") (pinfunction "7_7") (pintype "passive"))
    )
    (net (code "51") (name "Net-(IC6A-7D)") (class "Default")
      (node (ref "IC6") (pin "8") (pinfunction "7D_8") (pintype "input"))
      (node (ref "IC7") (pin "11") (pinfunction "P6_11") (pintype "bidirectional"))
      (node (ref "RN1") (pin "8") (pinfunction "8_8") (pintype "passive"))
    )
    (net (code "52") (name "Net-(IC6A-8D)") (class "Default")
      (node (ref "IC6") (pin "9") (pinfunction "8D_9") (pintype "input"))
      (node (ref "IC7") (pin "12") (pinfunction "P7_12") (pintype "bidirectional"))
      (node (ref "RN1") (pin "9") (pinfunction "9_9") (pintype "passive"))
    )
    (net (code "53") (name "Net-(IC8A-O)") (class "Default")
      (node (ref "IC8") (pin "12") (pinfunction "O_12") (pintype "output"))
      (node (ref "R4") (pin "P$1") (pinfunction "1_P$1") (pintype "passive"))
    )
    (net (code "54") (name "Net-(IC8B-O)") (class "Default")
      (node (ref "IC8") (pin "10") (pinfunction "O_10") (pintype "output"))
      (node (ref "R8") (pin "P$1") (pinfunction "1_P$1") (pintype "passive"))
    )
    (net (code "55") (name "Net-(IC8C-O)") (class "Default")
      (node (ref "IC8") (pin "8") (pinfunction "O_8") (pintype "output"))
      (node (ref "R12") (pin "P$1") (pinfunction "1_P$1") (pintype "passive"))
    )
    (net (code "56") (name "Net-(IC8D-O)") (class "Default")
      (node (ref "IC8") (pin "2") (pinfunction "O_2") (pintype "output"))
      (node (ref "R2") (pin "P$1") (pinfunction "1_P$1") (pintype "passive"))
    )
    (net (code "57") (name "Net-(IC8E-O)") (class "Default")
      (node (ref "IC8") (pin "4") (pinfunction "O_4") (pintype "output"))
      (node (ref "R6") (pin "P$1") (pinfunction "1_P$1") (pintype "passive"))
    )
    (net (code "58") (name "Net-(IC8F-O)") (class "Default")
      (node (ref "IC8") (pin "6") (pinfunction "O_6") (pintype "output"))
      (node (ref "R10") (pin "P$1") (pinfunction "1_P$1") (pintype "passive"))
    )
    (net (code "59") (name "Net-(IC9C-I1)") (class "Default")
      (node (ref "IC9") (pin "10") (pinfunction "I1_10") (pintype "input"))
      (node (ref "IC9") (pin "11") (pinfunction "O_11") (pintype "output"))
    )
    (net (code "60") (name "Net-(IC10--MR)") (class "Default")
      (node (ref "IC10") (pin "1") (pinfunction "-MR_1") (pintype "bidirectional"))
      (node (ref "IC10") (pin "5") (pinfunction "-PFO_5") (pintype "bidirectional"))
    )
    (net (code "61") (name "Net-(IC10--RESET)") (class "Default")
      (node (ref "IC10") (pin "7") (pinfunction "-RESET_7") (pintype "bidirectional"))
      (node (ref "IC9") (pin "5") (pinfunction "I1_5") (pintype "input"))
      (node (ref "J5") (pin "14") (pinfunction "14_14") (pintype "bidirectional"))
    )
    (net (code "62") (name "Net-(IC10-PFI)") (class "Default")
      (node (ref "IC10") (pin "4") (pinfunction "PFI_4") (pintype "bidirectional"))
      (node (ref "R18") (pin "P$2") (pinfunction "2_P$2") (pintype "passive"))
      (node (ref "R31") (pin "P$1") (pinfunction "1_P$1") (pintype "passive"))
    )
    (net (code "63") (name "Net-(IC11A-I)") (class "Default")
      (node (ref "IC11") (pin "13") (pinfunction "I_13") (pintype "input"))
      (node (ref "IC9") (pin "6") (pinfunction "O_6") (pintype "output"))
    )
    (net (code "64") (name "Net-(IC11A-O)") (class "Default")
      (node (ref "IC11") (pin "12") (pinfunction "O_12") (pintype "output"))
      (node (ref "IC9") (pin "2") (pinfunction "I1_2") (pintype "input"))
    )
    (net (code "65") (name "Net-(IC11B-O)") (class "Default")
      (node (ref "IC11") (pin "10") (pinfunction "O_10") (pintype "output"))
      (node (ref "LED") (pin "1") (pinfunction "1_1") (pintype "bidirectional"))
    )
    (net (code "66") (name "Net-(IC11D-I)") (class "Default")
      (node (ref "IC11") (pin "1") (pinfunction "I_1") (pintype "input"))
      (node (ref "IC9") (pin "3") (pinfunction "O_3") (pintype "output"))
    )
    (net (code "67") (name "Net-(IC11D-O)") (class "Default")
      (node (ref "IC11") (pin "2") (pinfunction "O_2") (pintype "output"))
      (node (ref "IC9") (pin "9") (pinfunction "I0_9") (pintype "input"))
    )
    (net (code "68") (name "Net-(IC12A-A)") (class "Default")
      (node (ref "IC12") (pin "3") (pinfunction "A_3") (pintype "bidirectional"))
      (node (ref "IC2") (pin "2") (pinfunction "Q6_2") (pintype "output"))
      (node (ref "JP1") (pin "2") (pinfunction "2_2") (pintype "bidirectional"))
    )
    (net (code "69") (name "Net-(O1-A)") (class "Default")
      (node (ref "O1") (pin "1") (pinfunction "A_1") (pintype "passive"))
      (node (ref "R23") (pin "P$1") (pinfunction "1_P$1") (pintype "passive"))
    )
    (net (code "70") (name "Net-(O1-C)") (class "Default")
      (node (ref "O1") (pin "2") (pinfunction "C_2") (pintype "passive"))
      (node (ref "SW-OFF") (pin "1") (pinfunction "1_1") (pintype "passive"))
    )
    (net (code "71") (name "Net-(O2-A)") (class "Default")
      (node (ref "O2") (pin "1") (pinfunction "A_1") (pintype "passive"))
      (node (ref "R24") (pin "P$1") (pinfunction "1_P$1") (pintype "passive"))
    )
    (net (code "72") (name "Net-(O2-C)") (class "Default")
      (node (ref "O2") (pin "2") (pinfunction "C_2") (pintype "passive"))
      (node (ref "SW-ON") (pin "1") (pinfunction "1_1") (pintype "passive"))
    )
    (net (code "73") (name "Net-(R2-2)") (class "Default")
      (node (ref "J-DRV4") (pin "1") (pinfunction "1_1") (pintype "passive"))
      (node (ref "R2") (pin "P$2") (pinfunction "2_P$2") (pintype "passive"))
    )
    (net (code "74") (name "Net-(R3-2)") (class "Default")
      (node (ref "J-DRV4") (pin "2") (pinfunction "2_2") (pintype "passive"))
      (node (ref "R3") (pin "P$2") (pinfunction "2_P$2") (pintype "passive"))
    )
    (net (code "75") (name "Net-(R4-2)") (class "Default")
      (node (ref "J-DRV4") (pin "3") (pinfunction "3_3") (pintype "passive"))
      (node (ref "R4") (pin "P$2") (pinfunction "2_P$2") (pintype "passive"))
    )
    (net (code "76") (name "Net-(R5-2)") (class "Default")
      (node (ref "J-DRV4") (pin "4") (pinfunction "4_4") (pintype "passive"))
      (node (ref "R5") (pin "P$2") (pinfunction "2_P$2") (pintype "passive"))
    )
    (net (code "77") (name "Net-(R6-2)") (class "Default")
      (node (ref "J-DRV3") (pin "1") (pinfunction "1_1") (pintype "passive"))
      (node (ref "R6") (pin "P$2") (pinfunction "2_P$2") (pintype "passive"))
    )
    (net (code "78") (name "Net-(R7-2)") (class "Default")
      (node (ref "J-DRV3") (pin "2") (pinfunction "2_2") (pintype "passive"))
      (node (ref "R7") (pin "P$2") (pinfunction "2_P$2") (pintype "passive"))
    )
    (net (code "79") (name "Net-(R8-2)") (class "Default")
      (node (ref "J-DRV3") (pin "3") (pinfunction "3_3") (pintype "passive"))
      (node (ref "R8") (pin "P$2") (pinfunction "2_P$2") (pintype "passive"))
    )
    (net (code "80") (name "Net-(R9-2)") (class "Default")
      (node (ref "J-DRV3") (pin "4") (pinfunction "4_4") (pintype "passive"))
      (node (ref "R9") (pin "P$2") (pinfunction "2_P$2") (pintype "passive"))
    )
    (net (code "81") (name "Net-(R10-2)") (class "Default")
      (node (ref "J-DRV2") (pin "1") (pinfunction "1_1") (pintype "passive"))
      (node (ref "R10") (pin "P$2") (pinfunction "2_P$2") (pintype "passive"))
    )
    (net (code "82") (name "Net-(R11-2)") (class "Default")
      (node (ref "J-DRV2") (pin "2") (pinfunction "2_2") (pintype "passive"))
      (node (ref "R11") (pin "P$2") (pinfunction "2_P$2") (pintype "passive"))
    )
    (net (code "83") (name "Net-(R12-2)") (class "Default")
      (node (ref "J-DRV2") (pin "3") (pinfunction "3_3") (pintype "passive"))
      (node (ref "R12") (pin "P$2") (pinfunction "2_P$2") (pintype "passive"))
    )
    (net (code "84") (name "Net-(R13-2)") (class "Default")
      (node (ref "J-DRV2") (pin "4") (pinfunction "4_4") (pintype "passive"))
      (node (ref "R13") (pin "P$2") (pinfunction "2_P$2") (pintype "passive"))
    )
    (net (code "85") (name "Net-(R14-2)") (class "Default")
      (node (ref "J-DRV1") (pin "1") (pinfunction "1_1") (pintype "passive"))
      (node (ref "R14") (pin "P$2") (pinfunction "2_P$2") (pintype "passive"))
    )
    (net (code "86") (name "Net-(R15-2)") (class "Default")
      (node (ref "J-DRV1") (pin "2") (pinfunction "2_2") (pintype "passive"))
      (node (ref "R15") (pin "P$2") (pinfunction "2_P$2") (pintype "passive"))
    )
    (net (code "87") (name "Net-(R16-2)") (class "Default")
      (node (ref "J-DRV1") (pin "3") (pinfunction "3_3") (pintype "passive"))
      (node (ref "R16") (pin "P$2") (pinfunction "2_P$2") (pintype "passive"))
    )
    (net (code "88") (name "Net-(R17-2)") (class "Default")
      (node (ref "J-DRV1") (pin "4") (pinfunction "4_4") (pintype "passive"))
      (node (ref "R17") (pin "P$2") (pinfunction "2_P$2") (pintype "passive"))
    )
    (net (code "89") (name "Net-(R25-2)") (class "Default")
      (node (ref "R25") (pin "P$2") (pinfunction "2_P$2") (pintype "passive"))
      (node (ref "SW-OFF") (pin "2") (pinfunction "2_2") (pintype "passive"))
    )
    (net (code "90") (name "Net-(R26-2)") (class "Default")
      (node (ref "R26") (pin "P$2") (pinfunction "2_P$2") (pintype "passive"))
      (node (ref "SW-ON") (pin "2") (pinfunction "2_2") (pintype "passive"))
    )
    (net (code "91") (name "Net-(R27-1)") (class "Default")
      (node (ref "J5") (pin "3") (pinfunction "3_3") (pintype "bidirectional"))
      (node (ref "R27") (pin "P$1") (pinfunction "1_P$1") (pintype "passive"))
    )
    (net (code "92") (name "Net-(R28-2)") (class "Default")
      (node (ref "LED") (pin "2") (pinfunction "2_2") (pintype "bidirectional"))
      (node (ref "R28") (pin "P$2") (pinfunction "2_P$2") (pintype "passive"))
      (node (ref "R33") (pin "P$1") (pinfunction "1_P$1") (pintype "passive"))
    )
    (net (code "93") (name "OFF") (class "Default")
      (node (ref "O1") (pin "4") (pinfunction "COL_4") (pintype "passive"))
      (node (ref "R19") (pin "P$1") (pinfunction "1_P$1") (pintype "passive"))
      (node (ref "R21") (pin "P$2") (pinfunction "2_P$2") (pintype "passive"))
    )
    (net (code "94") (name "ON") (class "Default")
      (node (ref "J5") (pin "18") (pinfunction "18_18") (pintype "bidirectional"))
      (node (ref "O2") (pin "4") (pinfunction "COL_4") (pintype "passive"))
      (node (ref "R20") (pin "P$1") (pinfunction "1_P$1") (pintype "passive"))
      (node (ref "R22") (pin "P$2") (pinfunction "2_P$2") (pintype "passive"))
    )
    (net (code "95") (name "SCL") (class "Default")
      (node (ref "IC7") (pin "14") (pinfunction "SCL_14") (pintype "input"))
      (node (ref "J5") (pin "7") (pinfunction "7_7") (pintype "bidirectional"))
      (node (ref "J5") (pin "8") (pinfunction "8_8") (pintype "bidirectional"))
    )
    (net (code "96") (name "SDA") (class "Default")
      (node (ref "IC7") (pin "15") (pinfunction "SDA_15") (pintype "bidirectional"))
      (node (ref "J5") (pin "5") (pinfunction "5_5") (pintype "bidirectional"))
      (node (ref "J5") (pin "6") (pinfunction "6_6") (pintype "bidirectional"))
    )
    (net (code "97") (name "SMALL_L") (class "Default")
      (node (ref "IC5") (pin "17") (pinfunction "3Q_17") (pintype "tri_state"))
      (node (ref "IC8") (pin "3") (pinfunction "I_3") (pintype "input"))
      (node (ref "R7") (pin "P$1") (pinfunction "1_P$1") (pintype "passive"))
    )
    (net (code "98") (name "SMALL_R") (class "Default")
      (node (ref "IC5") (pin "16") (pinfunction "4Q_16") (pintype "tri_state"))
      (node (ref "IC8") (pin "11") (pinfunction "I_11") (pintype "input"))
      (node (ref "R9") (pin "P$1") (pinfunction "1_P$1") (pintype "passive"))
    )
    (net (code "99") (name "SW_CLOCK") (class "Default")
      (node (ref "IC12") (pin "6") (pinfunction "~{A}/B_6") (pintype "input"))
      (node (ref "J5") (pin "13") (pinfunction "13_13") (pintype "bidirectional"))
      (node (ref "R29") (pin "P$2") (pinfunction "2_P$2") (pintype "passive"))
    )
    (net (code "100") (name "TINY_L") (class "Default")
      (node (ref "IC5") (pin "19") (pinfunction "1Q_19") (pintype "tri_state"))
      (node (ref "IC8") (pin "1") (pinfunction "I_1") (pintype "input"))
      (node (ref "R3") (pin "P$1") (pinfunction "1_P$1") (pintype "passive"))
    )
    (net (code "101") (name "TINY_R") (class "Default")
      (node (ref "IC5") (pin "18") (pinfunction "2Q_18") (pintype "tri_state"))
      (node (ref "IC8") (pin "13") (pinfunction "I_13") (pintype "input"))
      (node (ref "R5") (pin "P$1") (pinfunction "1_P$1") (pintype "passive"))
    )
    (net (code "102") (name "VCC") (class "Default")
      (node (ref "C1") (pin "1") (pinfunction "1_1") (pintype "passive"))
      (node (ref "C10") (pin "1") (pinfunction "1_1") (pintype "passive"))
      (node (ref "C11") (pin "1") (pinfunction "1_1") (pintype "passive"))
      (node (ref "C12") (pin "1") (pinfunction "1_1") (pintype "passive"))
      (node (ref "C13") (pin "1") (pinfunction "+_1") (pintype "passive"))
      (node (ref "C14") (pin "1") (pinfunction "1_1") (pintype "passive"))
      (node (ref "C22") (pin "1") (pinfunction "+_1") (pintype "passive"))
      (node (ref "C23") (pin "1") (pinfunction "1_1") (pintype "passive"))
      (node (ref "C4") (pin "1") (pinfunction "+_1") (pintype "passive"))
      (node (ref "C5") (pin "1") (pinfunction "1_1") (pintype "passive"))
      (node (ref "C6") (pin "1") (pinfunction "1_1") (pintype "passive"))
      (node (ref "C7") (pin "1") (pinfunction "1_1") (pintype "passive"))
      (node (ref "C8") (pin "1") (pinfunction "1_1") (pintype "passive"))
      (node (ref "C9") (pin "1") (pinfunction "1_1") (pintype "passive"))
      (node (ref "IC1") (pin "1") (pinfunction "VPP_1") (pintype "passive"))
      (node (ref "IC1") (pin "32") (pinfunction "VCC_32") (pintype "power_in"))
      (node (ref "IC10") (pin "2") (pinfunction "VCC_2") (pintype "bidirectional"))
      (node (ref "IC15") (pin "3") (pinfunction "VO_3") (pintype "passive"))
      (node (ref "IC2") (pin "16") (pinfunction "VDD_16") (pintype "power_in"))
      (node (ref "IC3") (pin "16") (pinfunction "VDD_16") (pintype "power_in"))
      (node (ref "IC7") (pin "1") (pinfunction "A0_1") (pintype "input"))
      (node (ref "IC7") (pin "16") (pinfunction "VDD_16") (pintype "power_in"))
      (node (ref "J5") (pin "11") (pinfunction "11_11") (pintype "bidirectional"))
      (node (ref "J5") (pin "12") (pinfunction "12_12") (pintype "bidirectional"))
      (node (ref "QG1") (pin "1") (pinfunction "E_1") (pintype "bidirectional"))
      (node (ref "QG1") (pin "8") (pinfunction "VCC_8") (pintype "power_in"))
      (node (ref "R19") (pin "P$2") (pinfunction "2_P$2") (pintype "passive"))
      (node (ref "R20") (pin "P$2") (pinfunction "2_P$2") (pintype "passive"))
      (node (ref "R28") (pin "P$1") (pinfunction "1_P$1") (pintype "passive"))
      (node (ref "R32") (pin "P$2") (pinfunction "2_P$2") (pintype "passive"))
      (node (ref "RN1") (pin "1") (pinfunction "1_1") (pintype "passive"))
      (node (ref "RN2") (pin "1") (pinfunction "1_1") (pintype "passive"))
    )
    (net (code "103") (name "X") (class "Default")
      (node (ref "D2") (pin "A") (pinfunction "A_A") (pintype "passive"))
      (node (ref "IC11") (pin "11") (pinfunction "I_11") (pintype "input"))
      (node (ref "IC9") (pin "12") (pinfunction "I0_12") (pintype "input"))
      (node (ref "IC9") (pin "8") (pinfunction "O_8") (pintype "output"))
    )
    (net (code "104") (name "unconnected-(IC2A-Q1-Pad9)") (class "Default")
      (node (ref "IC2") (pin "9") (pinfunction "Q1_9") (pintype "output"))
    )
    (net (code "105") (name "unconnected-(IC2A-Q2-Pad7)") (class "Default")
      (node (ref "IC2") (pin "7") (pinfunction "Q2_7") (pintype "output"))
    )
    (net (code "106") (name "unconnected-(IC2A-Q3-Pad6)") (class "Default")
      (node (ref "IC2") (pin "6") (pinfunction "Q3_6") (pintype "output"))
    )
    (net (code "107") (name "unconnected-(IC2A-Q4-Pad5)") (class "Default")
      (node (ref "IC2") (pin "5") (pinfunction "Q4_5") (pintype "output"))
    )
    (net (code "108") (name "unconnected-(IC2A-Q5-Pad3)") (class "Default")
      (node (ref "IC2") (pin "3") (pinfunction "Q5_3") (pintype "output"))
    )
    (net (code "109") (name "unconnected-(IC2A-Q7-Pad4)") (class "Default")
      (node (ref "IC2") (pin "4") (pinfunction "Q7_4") (pintype "output"))
    )
    (net (code "110") (name "unconnected-(IC2A-Q8-Pad13)") (class "Default")
      (node (ref "IC2") (pin "13") (pinfunction "Q8_13") (pintype "output"))
    )
    (net (code "111") (name "unconnected-(IC2A-Q9-Pad12)") (class "Default")
      (node (ref "IC2") (pin "12") (pinfunction "Q9_12") (pintype "output"))
    )
    (net (code "112") (name "unconnected-(IC2A-Q10-Pad14)") (class "Default")
      (node (ref "IC2") (pin "14") (pinfunction "Q10_14") (pintype "output"))
    )
    (net (code "113") (name "unconnected-(IC2A-Q11-Pad15)") (class "Default")
      (node (ref "IC2") (pin "15") (pinfunction "Q11_15") (pintype "output"))
    )
    (net (code "114") (name "unconnected-(IC2A-Q12-Pad1)") (class "Default")
      (node (ref "IC2") (pin "1") (pinfunction "Q12_1") (pintype "output"))
    )
    (net (code "115") (name "unconnected-(IC3A-Q12-Pad1)") (class "Default")
      (node (ref "IC3") (pin "1") (pinfunction "Q12_1") (pintype "output"))
    )
    (net (code "116") (name "unconnected-(IC4D-I-Pad1)") (class "Default")
      (node (ref "IC4") (pin "1") (pinfunction "I_1") (pintype "input"))
    )
    (net (code "117") (name "unconnected-(IC4D-O-Pad2)") (class "Default")
      (node (ref "IC4") (pin "2") (pinfunction "O_2") (pintype "output"))
    )
    (net (code "118") (name "unconnected-(IC7-~{INT}-Pad13)") (class "Default")
      (node (ref "IC7") (pin "13") (pinfunction "~{INT}_13") (pintype "output"))
    )
    (net (code "119") (name "unconnected-(IC10--WDO-Pad8)") (class "Default")
      (node (ref "IC10") (pin "8") (pinfunction "-WDO_8") (pintype "bidirectional"))
    )
    (net (code "120") (name "unconnected-(IC10-WDI-Pad6)") (class "Default")
      (node (ref "IC10") (pin "6") (pinfunction "WDI_6") (pintype "bidirectional"))
    )
    (net (code "121") (name "unconnected-(IC11C-I-Pad9)") (class "Default")
      (node (ref "IC11") (pin "9") (pinfunction "I_9") (pintype "input"))
    )
    (net (code "122") (name "unconnected-(IC11C-O-Pad8)") (class "Default")
      (node (ref "IC11") (pin "8") (pinfunction "O_8") (pintype "output"))
    )
    (net (code "123") (name "unconnected-(IC11E-I-Pad3)") (class "Default")
      (node (ref "IC11") (pin "3") (pinfunction "I_3") (pintype "input"))
    )
    (net (code "124") (name "unconnected-(IC11E-O-Pad4)") (class "Default")
      (node (ref "IC11") (pin "4") (pinfunction "O_4") (pintype "output"))
    )
    (net (code "125") (name "unconnected-(IC11F-I-Pad5)") (class "Default")
      (node (ref "IC11") (pin "5") (pinfunction "I_5") (pintype "input"))
    )
    (net (code "126") (name "unconnected-(IC11F-O-Pad6)") (class "Default")
      (node (ref "IC11") (pin "6") (pinfunction "O_6") (pintype "output"))
    )
  )
)
